# Kivipallur_joonis3.net
KiCad netlist of a schematic drawn in Altium Designer
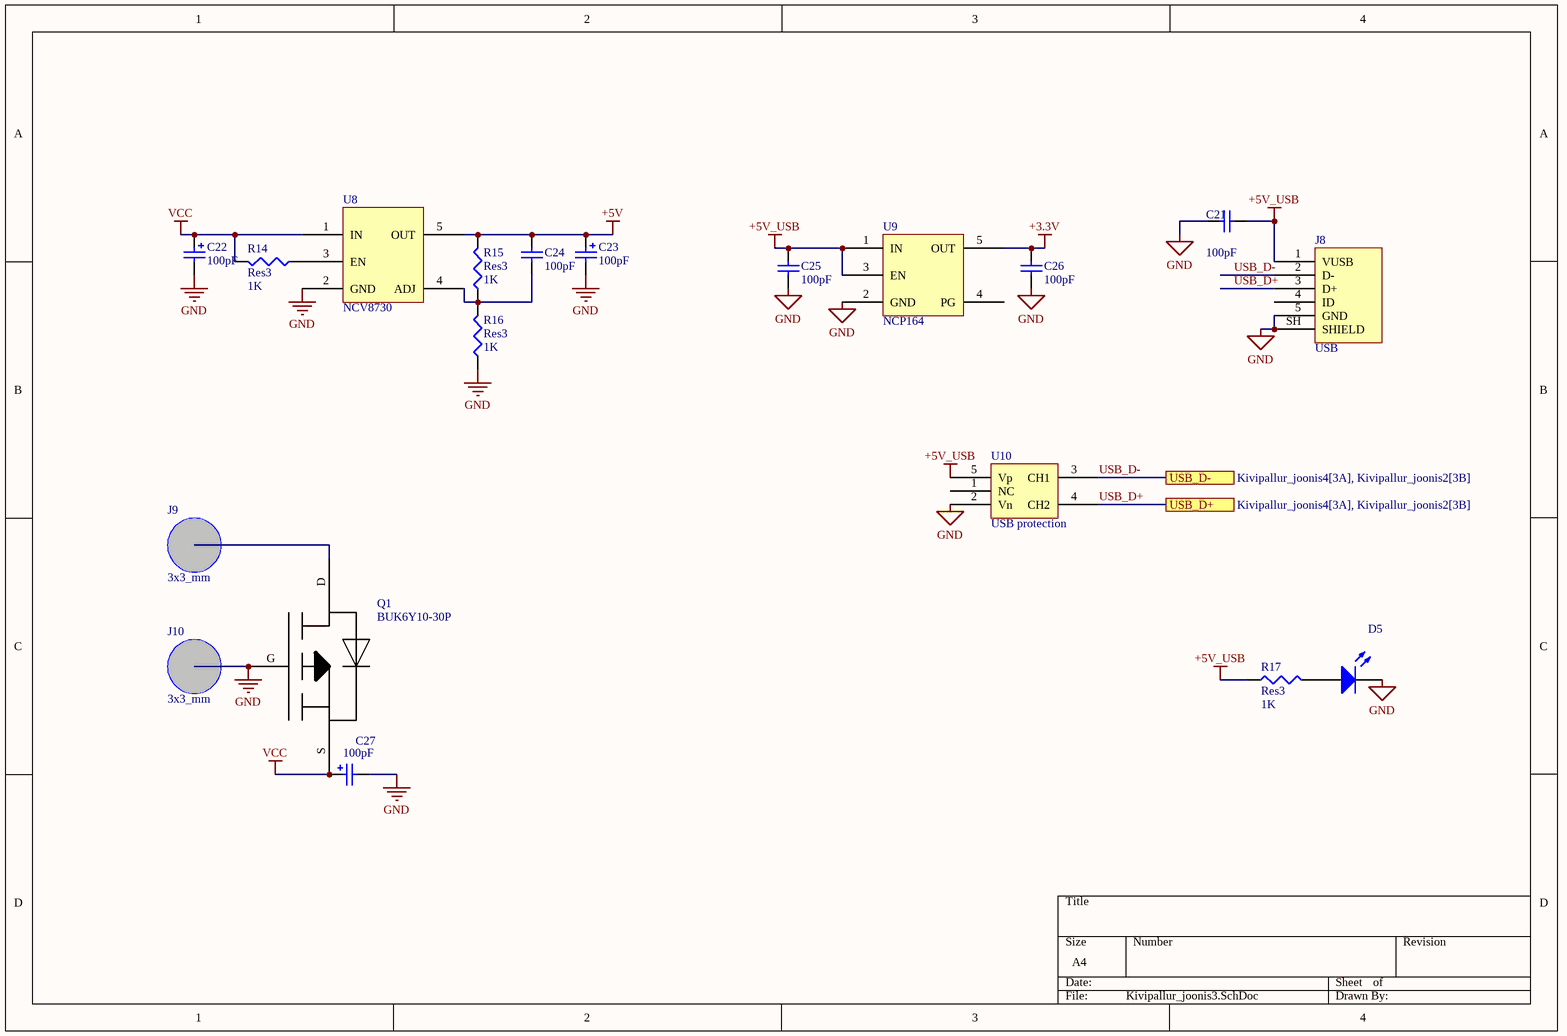
[diagram p0: Kivipallur_joonis3.SchDoc]

(export (version "E")
  (design (tool "Eeschema 10.0.6"))
  (components
    (comp (ref "C21")
      (value "100pF")
      (footprint "C1206")
      (description "Capacitor (Semiconductor SIM Model)")
      (fields (field (name "Comment") "Cap Semi") (field (name "PUBLISHER") "Altium Limited"))
      (libsource (lib "Miscellaneous Devices") (part "Cap Semi"))
    )
    (comp (ref "C22")
      (value "100pF")
      (footprint "C0805")
      (description "Polarized Capacitor (Surface Mount)")
      (fields (field (name "Comment") "Cap Pol3") (field (name "PUBLISHER") "Altium Limited"))
      (libsource (lib "Miscellaneous Devices") (part "Cap Pol3"))
    )
    (comp (ref "C23")
      (value "100pF")
      (footprint "C0805")
      (description "Polarized Capacitor (Surface Mount)")
      (fields (field (name "Comment") "Cap Pol3") (field (name "PUBLISHER") "Altium Limited"))
      (libsource (lib "Miscellaneous Devices") (part "Cap Pol3"))
    )
    (comp (ref "C24")
      (value "100pF")
      (footprint "C1206")
      (description "Capacitor (Semiconductor SIM Model)")
      (fields (field (name "Comment") "Cap Semi") (field (name "PUBLISHER") "Altium Limited"))
      (libsource (lib "Miscellaneous Devices") (part "Cap Semi"))
    )
    (comp (ref "C25")
      (value "100pF")
      (footprint "C1206")
      (description "Capacitor (Semiconductor SIM Model)")
      (fields (field (name "Comment") "Cap Semi") (field (name "PUBLISHER") "Altium Limited"))
      (libsource (lib "Miscellaneous Devices") (part "Cap Semi"))
    )
    (comp (ref "C26")
      (value "100pF")
      (footprint "C1206")
      (description "Capacitor (Semiconductor SIM Model)")
      (fields (field (name "Comment") "Cap Semi") (field (name "PUBLISHER") "Altium Limited"))
      (libsource (lib "Miscellaneous Devices") (part "Cap Semi"))
    )
    (comp (ref "C27")
      (value "100pF")
      (footprint "C0805")
      (description "Polarized Capacitor (Surface Mount)")
      (fields (field (name "Comment") "Cap Pol3") (field (name "PUBLISHER") "Altium Limited"))
      (libsource (lib "Miscellaneous Devices") (part "Cap Pol3"))
    )
    (comp (ref "D5")
      (value "LED3")
      (footprint "3.5X2.8X1.9")
      (description "Typical BLUE SiC LED")
      (fields (field (name "PUBLISHER") "Altium Limited"))
      (libsource (lib "Miscellaneous Devices") (part "LED3"))
    )
    (comp (ref "J8") (value "USB") (footprint "USB") (libsource (lib "USB") (part "USB")))
    (comp (ref "J9") (value "3x3_mm") (footprint "3x3_mm") (libsource (lib "3x3_mm") (part "3x3_mm")))
    (comp (ref "J10") (value "3x3_mm") (footprint "3x3_mm") (libsource (lib "3x3_mm") (part "3x3_mm")))
    (comp (ref "Q1")
      (value "BUK6Y10-30P")
      (footprint "BUK6Y10-30P")
      (libsource (lib "BUK6Y10-30P") (part "BUK6Y10-30P"))
    )
    (comp (ref "R14")
      (value "Res3")
      (footprint "J1-0603")
      (description "Resistor")
      (fields (field (name "ALTIUM_VALUE") "1K") (field (name "PUBLISHER") "Altium Limited"))
      (libsource (lib "Miscellaneous Devices") (part "Res3"))
    )
    (comp (ref "R15")
      (value "Res3")
      (footprint "J1-0603")
      (description "Resistor")
      (fields (field (name "ALTIUM_VALUE") "1K") (field (name "PUBLISHER") "Altium Limited"))
      (libsource (lib "Miscellaneous Devices") (part "Res3"))
    )
    (comp (ref "R16")
      (value "Res3")
      (footprint "J1-0603")
      (description "Resistor")
      (fields (field (name "ALTIUM_VALUE") "1K") (field (name "PUBLISHER") "Altium Limited"))
      (libsource (lib "Miscellaneous Devices") (part "Res3"))
    )
    (comp (ref "R17")
      (value "Res3")
      (footprint "J1-0603")
      (description "Resistor")
      (fields (field (name "ALTIUM_VALUE") "1K") (field (name "PUBLISHER") "Altium Limited"))
      (libsource (lib "Miscellaneous Devices") (part "Res3"))
    )
    (comp (ref "U8") (value "NCV8730") (footprint "NCV8730") (libsource (lib "NCV8730") (part "NCV8730")))
    (comp (ref "U9") (value "NCP164") (footprint "NCP164") (libsource (lib "NCP164") (part "NCP164")))
    (comp (ref "U10")
      (value "USB protection")
      (footprint "USB protection")
      (libsource (lib "USB protection") (part "USB protection"))
    )
  )
  (nets
    (net (code "1") (name "+3.3V") (class "Default")
      (node (ref "C26") (pin "1") (pinfunction "1_1") (pintype "passive"))
      (node (ref "U9") (pin "5") (pinfunction "OUT_5") (pintype "power_in"))
    )
    (net (code "2") (name "+5V") (class "Default")
      (node (ref "C23") (pin "1") (pinfunction "1_1") (pintype "passive"))
      (node (ref "C24") (pin "1") (pinfunction "1_1") (pintype "passive"))
      (node (ref "R15") (pin "2") (pinfunction "2_2") (pintype "passive"))
      (node (ref "U8") (pin "5") (pinfunction "OUT_5") (pintype "power_in"))
    )
    (net (code "3") (name "+5V_USB") (class "Default")
      (node (ref "C21") (pin "1") (pinfunction "1_1") (pintype "passive"))
      (node (ref "C25") (pin "1") (pinfunction "1_1") (pintype "passive"))
      (node (ref "J8") (pin "1") (pinfunction "VUSB_1") (pintype "passive"))
      (node (ref "R17") (pin "1") (pinfunction "1_1") (pintype "passive"))
      (node (ref "U10") (pin "5") (pinfunction "Vp_5") (pintype "passive"))
      (node (ref "U9") (pin "1") (pinfunction "IN_1") (pintype "power_in"))
      (node (ref "U9") (pin "3") (pinfunction "EN_3") (pintype "passive"))
    )
    (net (code "4") (name "/USB_D+") (class "Default")
      (node (ref "J8") (pin "3") (pinfunction "D+_3") (pintype "passive"))
      (node (ref "U10") (pin "4") (pinfunction "CH2_4") (pintype "passive"))
    )
    (net (code "5") (name "/USB_D-") (class "Default")
      (node (ref "J8") (pin "2") (pinfunction "D-_2") (pintype "passive"))
      (node (ref "U10") (pin "3") (pinfunction "CH1_3") (pintype "passive"))
    )
    (net (code "6") (name "GND") (class "Default")
      (node (ref "C21") (pin "2") (pinfunction "2_2") (pintype "passive"))
      (node (ref "C22") (pin "2") (pinfunction "2_2") (pintype "passive"))
      (node (ref "C23") (pin "2") (pinfunction "2_2") (pintype "passive"))
      (node (ref "C25") (pin "2") (pinfunction "2_2") (pintype "passive"))
      (node (ref "C26") (pin "2") (pinfunction "2_2") (pintype "passive"))
      (node (ref "C27") (pin "2") (pinfunction "2_2") (pintype "passive"))
      (node (ref "D5") (pin "2") (pinfunction "K_2") (pintype "passive"))
      (node (ref "J8") (pin "5") (pinfunction "GND_5") (pintype "passive"))
      (node (ref "J8") (pin "SH") (pinfunction "SHIELD_SH") (pintype "passive"))
      (node (ref "Q1") (pin "G") (pintype "passive"))
      (node (ref "R16") (pin "1") (pinfunction "1_1") (pintype "passive"))
      (node (ref "U10") (pin "2") (pinfunction "Vn_2") (pintype "passive"))
      (node (ref "U8") (pin "2") (pinfunction "GND_2") (pintype "power_in"))
      (node (ref "U9") (pin "2") (pinfunction "GND_2") (pintype "power_in"))
    )
    (net (code "7") (name "Net-(D5-A)") (class "Default")
      (node (ref "D5") (pin "1") (pinfunction "A_1") (pintype "passive"))
      (node (ref "R17") (pin "2") (pinfunction "2_2") (pintype "passive"))
    )
    (net (code "8") (name "Net-(U8-ADJ)") (class "Default")
      (node (ref "C24") (pin "2") (pinfunction "2_2") (pintype "passive"))
      (node (ref "R15") (pin "1") (pinfunction "1_1") (pintype "passive"))
      (node (ref "R16") (pin "2") (pinfunction "2_2") (pintype "passive"))
      (node (ref "U8") (pin "4") (pinfunction "ADJ_4") (pintype "passive"))
    )
    (net (code "9") (name "Net-(U8-EN)") (class "Default")
      (node (ref "R14") (pin "1") (pinfunction "1_1") (pintype "passive"))
      (node (ref "U8") (pin "3") (pinfunction "EN_3") (pintype "passive"))
    )
    (net (code "10") (name "VCC") (class "Default")
      (node (ref "C22") (pin "1") (pinfunction "1_1") (pintype "passive"))
      (node (ref "C27") (pin "1") (pinfunction "1_1") (pintype "passive"))
      (node (ref "Q1") (pin "S") (pintype "passive"))
      (node (ref "R14") (pin "2") (pinfunction "2_2") (pintype "passive"))
      (node (ref "U8") (pin "1") (pinfunction "IN_1") (pintype "power_in"))
    )
    (net (code "11") (name "unconnected-(J8-ID-Pad4)") (class "Default")
      (node (ref "J8") (pin "4") (pinfunction "ID_4") (pintype "passive"))
    )
    (net (code "12") (name "unconnected-(Q1-PadD)") (class "Default")
      (node (ref "Q1") (pin "D") (pintype "passive"))
    )
    (net (code "13") (name "unconnected-(U9-PG-Pad4)") (class "Default")
      (node (ref "U9") (pin "4") (pinfunction "PG_4") (pintype "passive"))
    )
    (net (code "14") (name "unconnected-(U10-NC-Pad1)") (class "Default")
      (node (ref "U10") (pin "1") (pinfunction "NC_1") (pintype "passive"))
    )
  )
)
